# board.net
KiCad netlist of a schematic drawn in EAGLE
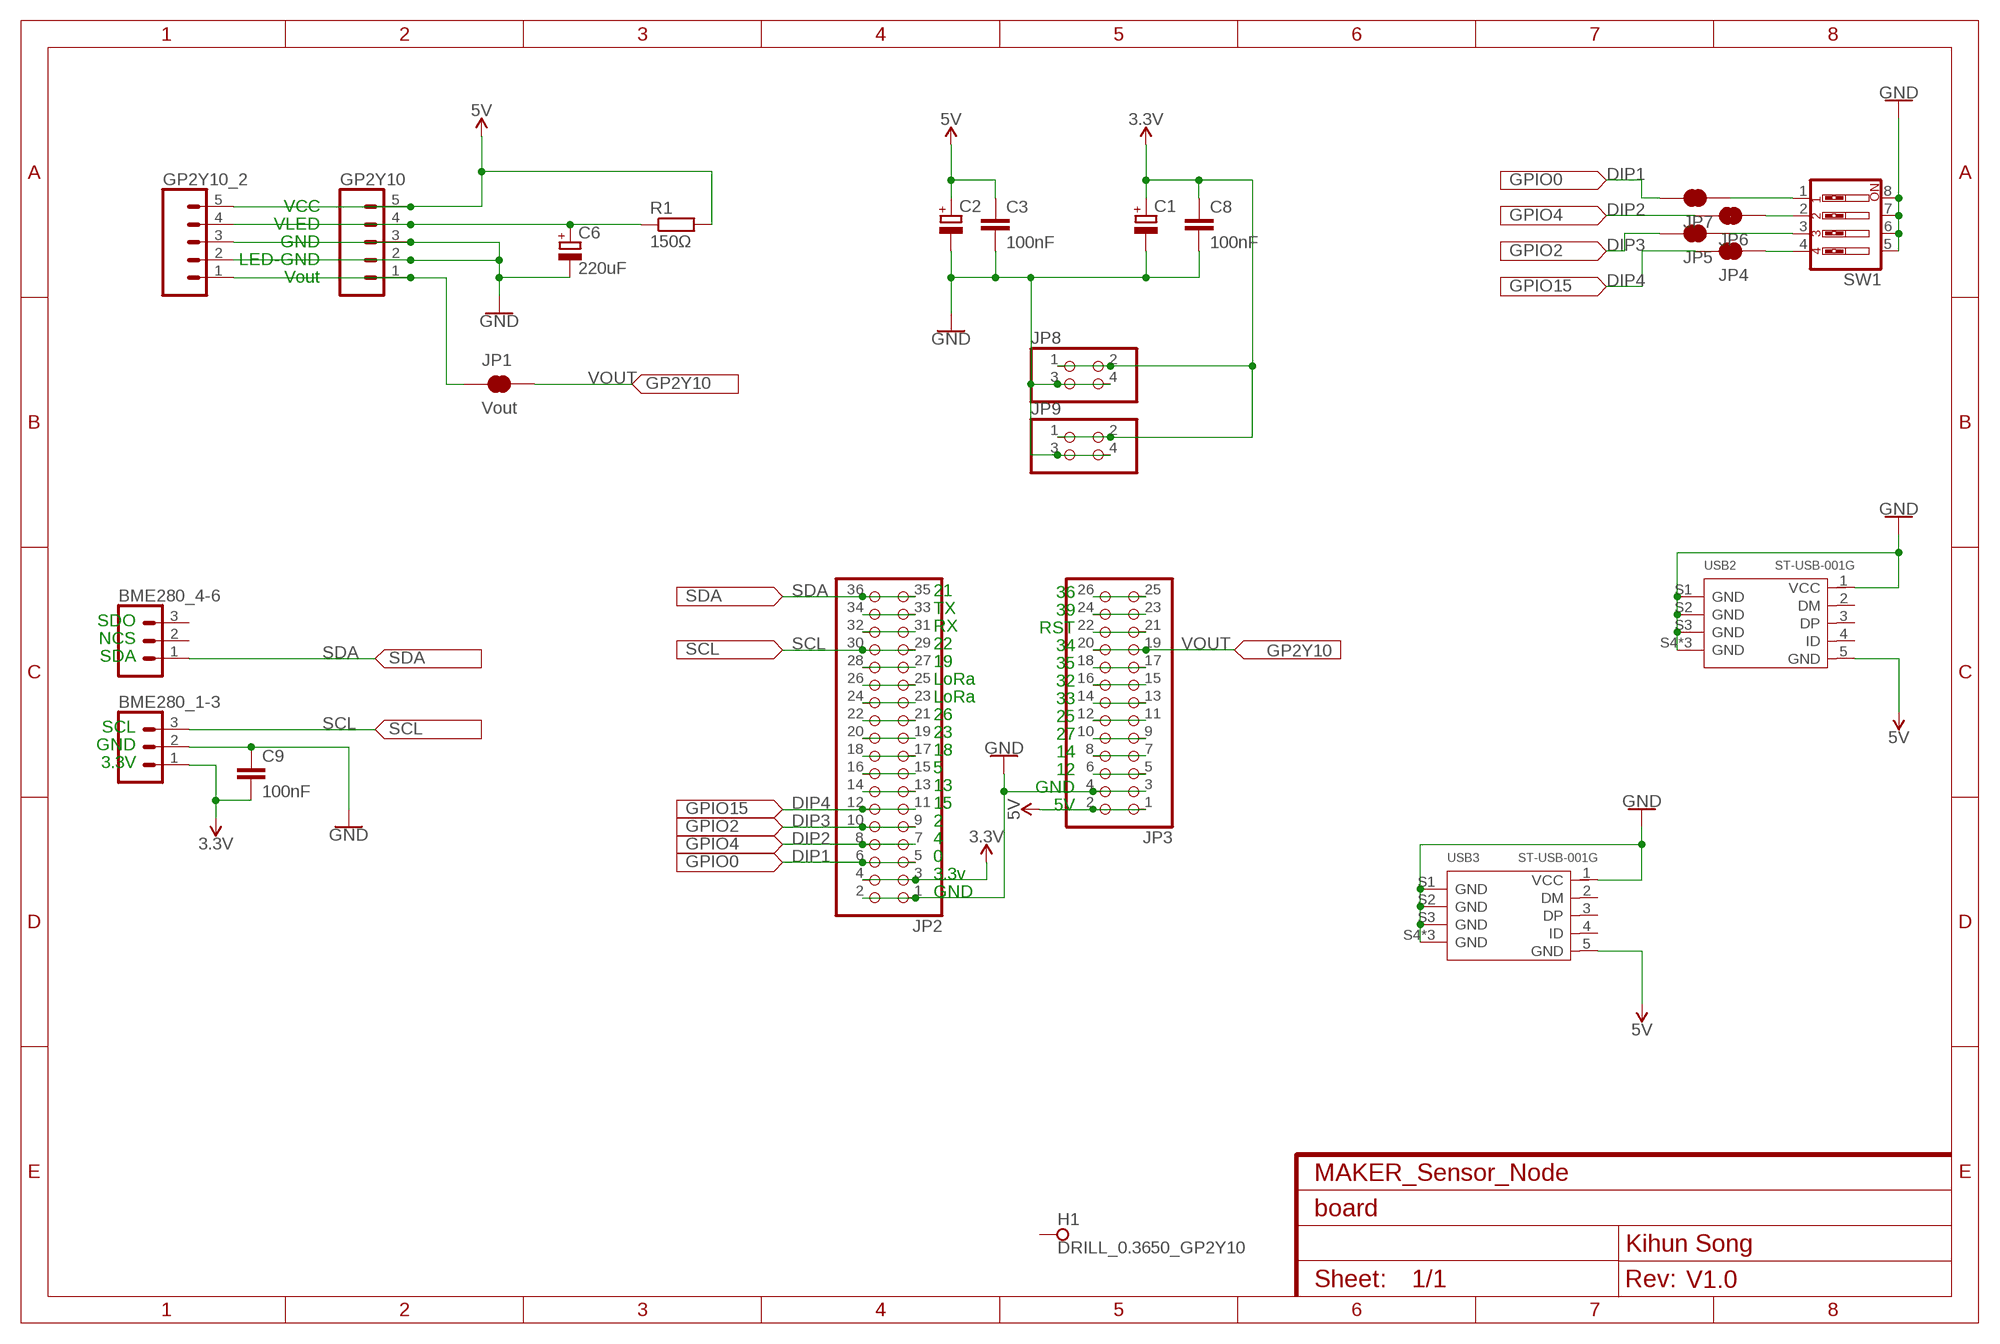
[diagram p0: schematic, sheet 1]

(export (version "E")
  (design (tool "Eeschema 10.0.6"))
  (components
    (comp (ref "BME280_1-3")
      (value "CONN_03")
      (footprint "eagle-import:1X03")
      (libsource (lib "eagle-import") (part "CONN_03"))
    )
    (comp (ref "BME280_4-6")
      (value "CONN_03")
      (footprint "eagle-import:1X03")
      (libsource (lib "eagle-import") (part "CONN_03"))
    )
    (comp (ref "C1")
      (value "CPOL-EUD")
      (footprint "eagle-import:PANASONIC_D")
      (libsource (lib "eagle-import") (part "CPOL-EUD"))
    )
    (comp (ref "C2")
      (value "CPOL-EUD")
      (footprint "eagle-import:PANASONIC_D")
      (libsource (lib "eagle-import") (part "CPOL-EUD"))
    )
    (comp (ref "C3")
      (value "100nF")
      (footprint "eagle-import:C0805")
      (libsource (lib "eagle-import") (part "C-EUC0805"))
    )
    (comp (ref "C6")
      (value "220uF")
      (footprint "eagle-import:E2,5-5")
      (libsource (lib "eagle-import") (part "CPOL-EUE2.5-5"))
    )
    (comp (ref "C8")
      (value "100nF")
      (footprint "eagle-import:C0805")
      (libsource (lib "eagle-import") (part "C-EUC0805"))
    )
    (comp (ref "C9")
      (value "100nF")
      (footprint "eagle-import:C0805")
      (libsource (lib "eagle-import") (part "C-EUC0805"))
    )
    (comp (ref "GP2Y10")
      (value "CONN_05")
      (footprint "eagle-import:1X05")
      (libsource (lib "eagle-import") (part "CONN_05"))
    )
    (comp (ref "GP2Y10_2")
      (value "CONN_05PTH_LONGPADS")
      (footprint "eagle-import:1X05_LONGPADS")
      (libsource (lib "eagle-import") (part "CONN_05PTH_LONGPADS"))
    )
    (comp (ref "H1")
      (value "DRILL_0.3650_GP2Y10")
      (footprint "eagle-import:PAD_0.3650")
      (libsource (lib "eagle-import") (part "SPECIAL_DRILL_0.3650"))
    )
    (comp (ref "JP1")
      (value "Vout")
      (footprint "eagle-import:SMT-JUMPER_2_NC_TRACE_SILK")
      (libsource (lib "eagle-import") (part "JUMPER-SMT_2_NC_TRACE_SILK"))
    )
    (comp (ref "JP2")
      (value "PINHD-2X18")
      (footprint "eagle-import:2X18")
      (libsource (lib "eagle-import") (part "PINHD-2X18"))
    )
    (comp (ref "JP3")
      (value "PINHD-2X13")
      (footprint "eagle-import:2X13")
      (libsource (lib "eagle-import") (part "PINHD-2X13"))
    )
    (comp (ref "JP4")
      (value "JUMPER-SMT_2_NC_TRACE_SILK")
      (footprint "eagle-import:SMT-JUMPER_2_NC_TRACE_SILK")
      (libsource (lib "eagle-import") (part "JUMPER-SMT_2_NC_TRACE_SILK"))
    )
    (comp (ref "JP5")
      (value "JUMPER-SMT_2_NC_TRACE_SILK")
      (footprint "eagle-import:SMT-JUMPER_2_NC_TRACE_SILK")
      (libsource (lib "eagle-import") (part "JUMPER-SMT_2_NC_TRACE_SILK"))
    )
    (comp (ref "JP6")
      (value "JUMPER-SMT_2_NC_TRACE_SILK")
      (footprint "eagle-import:SMT-JUMPER_2_NC_TRACE_SILK")
      (libsource (lib "eagle-import") (part "JUMPER-SMT_2_NC_TRACE_SILK"))
    )
    (comp (ref "JP7")
      (value "JUMPER-SMT_2_NC_TRACE_SILK")
      (footprint "eagle-import:SMT-JUMPER_2_NC_TRACE_SILK")
      (libsource (lib "eagle-import") (part "JUMPER-SMT_2_NC_TRACE_SILK"))
    )
    (comp (ref "JP8")
      (value "PINHD-2X2/OCT")
      (footprint "eagle-import:2X02")
      (libsource (lib "eagle-import") (part "PINHD-2X2/OCT"))
    )
    (comp (ref "JP9")
      (value "PINHD-2X2/OCT")
      (footprint "eagle-import:2X02")
      (libsource (lib "eagle-import") (part "PINHD-2X2/OCT"))
    )
    (comp (ref "R1")
      (value "150Ω")
      (footprint "eagle-import:0204_7")
      (libsource (lib "eagle-import") (part "R-EU_0204/7"))
    )
    (comp (ref "SW1")
      (value "SW_DIP-4")
      (footprint "eagle-import:EDG-04")
      (libsource (lib "eagle-import") (part "SW_DIP-4"))
    )
    (comp (ref "USB2")
      (value "ST-USB-001G")
      (footprint "eagle-import:MICRO-USB5+4P-SMD-0.65-B")
      (libsource (lib "eagle-import") (part "MICRO-USB-SMD-B-WITHOUT-POST-W/P(ST-USB-001G)"))
    )
    (comp (ref "USB3")
      (value "ST-USB-001G")
      (footprint "eagle-import:MICRO-USB5+4P-SMD-0.65-B")
      (libsource (lib "eagle-import") (part "MICRO-USB-SMD-B-WITHOUT-POST-W/P(ST-USB-001G)"))
    )
  )
  (nets
    (net (code "1") (name "/DIP1") (class "Default")
      (node (ref "JP2") (pin "5") (pinfunction "5_5") (pintype "passive"))
      (node (ref "JP2") (pin "6") (pinfunction "6_6") (pintype "passive"))
      (node (ref "JP7") (pin "2") (pinfunction "2_2") (pintype "passive"))
    )
    (net (code "2") (name "/DIP2") (class "Default")
      (node (ref "JP2") (pin "7") (pinfunction "7_7") (pintype "passive"))
      (node (ref "JP2") (pin "8") (pinfunction "8_8") (pintype "passive"))
      (node (ref "JP6") (pin "2") (pinfunction "2_2") (pintype "passive"))
    )
    (net (code "3") (name "/DIP3") (class "Default")
      (node (ref "JP2") (pin "10") (pinfunction "10_10") (pintype "passive"))
      (node (ref "JP2") (pin "9") (pinfunction "9_9") (pintype "passive"))
      (node (ref "JP5") (pin "2") (pinfunction "2_2") (pintype "passive"))
    )
    (net (code "4") (name "/DIP4") (class "Default")
      (node (ref "JP2") (pin "11") (pinfunction "11_11") (pintype "passive"))
      (node (ref "JP2") (pin "12") (pinfunction "12_12") (pintype "passive"))
      (node (ref "JP4") (pin "2") (pinfunction "2_2") (pintype "passive"))
    )
    (net (code "5") (name "/SCL") (class "Default")
      (node (ref "BME280_1-3") (pin "3") (pinfunction "3_3") (pintype "passive"))
      (node (ref "JP2") (pin "29") (pinfunction "29_29") (pintype "passive"))
      (node (ref "JP2") (pin "30") (pinfunction "30_30") (pintype "passive"))
    )
    (net (code "6") (name "/SDA") (class "Default")
      (node (ref "BME280_4-6") (pin "1") (pinfunction "1_1") (pintype "passive"))
      (node (ref "JP2") (pin "35") (pinfunction "35_35") (pintype "passive"))
      (node (ref "JP2") (pin "36") (pinfunction "36_36") (pintype "passive"))
    )
    (net (code "7") (name "/VOUT") (class "Default")
      (node (ref "JP1") (pin "2") (pinfunction "2_2") (pintype "passive"))
      (node (ref "JP3") (pin "19") (pinfunction "19_19") (pintype "passive"))
      (node (ref "JP3") (pin "20") (pinfunction "20_20") (pintype "passive"))
    )
    (net (code "8") (name "3.3V") (class "Default")
      (node (ref "BME280_1-3") (pin "1") (pinfunction "1_1") (pintype "passive"))
      (node (ref "C1") (pin "+") (pinfunction "+_+") (pintype "passive"))
      (node (ref "C8") (pin "1") (pinfunction "1_1") (pintype "passive"))
      (node (ref "C9") (pin "2") (pinfunction "2_2") (pintype "passive"))
      (node (ref "JP2") (pin "3") (pinfunction "3_3") (pintype "passive"))
      (node (ref "JP2") (pin "4") (pinfunction "4_4") (pintype "passive"))
      (node (ref "JP8") (pin "1") (pinfunction "1_1") (pintype "passive"))
      (node (ref "JP8") (pin "2") (pinfunction "2_2") (pintype "passive"))
      (node (ref "JP9") (pin "1") (pinfunction "1_1") (pintype "passive"))
      (node (ref "JP9") (pin "2") (pinfunction "2_2") (pintype "passive"))
    )
    (net (code "9") (name "5V") (class "Default")
      (node (ref "C2") (pin "+") (pinfunction "+_+") (pintype "passive"))
      (node (ref "C3") (pin "1") (pinfunction "1_1") (pintype "passive"))
      (node (ref "GP2Y10") (pin "5") (pinfunction "5_5") (pintype "passive"))
      (node (ref "GP2Y10_2") (pin "5") (pinfunction "5_5") (pintype "passive"))
      (node (ref "JP3") (pin "1") (pinfunction "1_1") (pintype "passive"))
      (node (ref "JP3") (pin "2") (pinfunction "2_2") (pintype "passive"))
      (node (ref "R1") (pin "2") (pinfunction "2_2") (pintype "passive"))
      (node (ref "USB2") (pin "5") (pinfunction "GND_5") (pintype "bidirectional"))
      (node (ref "USB3") (pin "5") (pinfunction "GND_5") (pintype "bidirectional"))
    )
    (net (code "10") (name "GND") (class "Default")
      (node (ref "BME280_1-3") (pin "2") (pinfunction "2_2") (pintype "passive"))
      (node (ref "C1") (pin "-") (pinfunction "-_-") (pintype "passive"))
      (node (ref "C2") (pin "-") (pinfunction "-_-") (pintype "passive"))
      (node (ref "C3") (pin "2") (pinfunction "2_2") (pintype "passive"))
      (node (ref "C6") (pin "-") (pinfunction "-_-") (pintype "passive"))
      (node (ref "C8") (pin "2") (pinfunction "2_2") (pintype "passive"))
      (node (ref "C9") (pin "1") (pinfunction "1_1") (pintype "passive"))
      (node (ref "GP2Y10") (pin "2") (pinfunction "2_2") (pintype "passive"))
      (node (ref "GP2Y10") (pin "3") (pinfunction "3_3") (pintype "passive"))
      (node (ref "GP2Y10_2") (pin "2") (pinfunction "2_2") (pintype "passive"))
      (node (ref "GP2Y10_2") (pin "3") (pinfunction "3_3") (pintype "passive"))
      (node (ref "JP2") (pin "1") (pinfunction "1_1") (pintype "passive"))
      (node (ref "JP2") (pin "2") (pinfunction "2_2") (pintype "passive"))
      (node (ref "JP3") (pin "3") (pinfunction "3_3") (pintype "passive"))
      (node (ref "JP3") (pin "4") (pinfunction "4_4") (pintype "passive"))
      (node (ref "JP8") (pin "3") (pinfunction "3_3") (pintype "passive"))
      (node (ref "JP8") (pin "4") (pinfunction "4_4") (pintype "passive"))
      (node (ref "JP9") (pin "3") (pinfunction "3_3") (pintype "passive"))
      (node (ref "JP9") (pin "4") (pinfunction "4_4") (pintype "passive"))
      (node (ref "SW1") (pin "5") (pinfunction "5_5") (pintype "passive"))
      (node (ref "SW1") (pin "6") (pinfunction "6_6") (pintype "passive"))
      (node (ref "SW1") (pin "7") (pinfunction "7_7") (pintype "passive"))
      (node (ref "SW1") (pin "8") (pinfunction "8_8") (pintype "passive"))
      (node (ref "USB2") (pin "1") (pinfunction "VCC_1") (pintype "bidirectional"))
      (node (ref "USB2") (pin "S1") (pinfunction "GND_S1") (pintype "bidirectional"))
      (node (ref "USB2") (pin "S2") (pinfunction "GND_S2") (pintype "bidirectional"))
      (node (ref "USB2") (pin "S3") (pinfunction "GND_S3") (pintype "bidirectional"))
      (node (ref "USB2") (pin "S4") (pinfunction "GND_S4") (pintype "bidirectional"))
      (node (ref "USB2") (pin "S5") (pinfunction "GND_S5") (pintype "bidirectional"))
      (node (ref "USB2") (pin "S6") (pinfunction "GND_S6") (pintype "bidirectional"))
      (node (ref "USB3") (pin "1") (pinfunction "VCC_1") (pintype "bidirectional"))
      (node (ref "USB3") (pin "S1") (pinfunction "GND_S1") (pintype "bidirectional"))
      (node (ref "USB3") (pin "S2") (pinfunction "GND_S2") (pintype "bidirectional"))
      (node (ref "USB3") (pin "S3") (pinfunction "GND_S3") (pintype "bidirectional"))
      (node (ref "USB3") (pin "S4") (pinfunction "GND_S4") (pintype "bidirectional"))
      (node (ref "USB3") (pin "S5") (pinfunction "GND_S5") (pintype "bidirectional"))
      (node (ref "USB3") (pin "S6") (pinfunction "GND_S6") (pintype "bidirectional"))
    )
    (net (code "11") (name "Net-(C6-Pad+)") (class "Default")
      (node (ref "C6") (pin "+") (pinfunction "+_+") (pintype "passive"))
      (node (ref "GP2Y10") (pin "4") (pinfunction "4_4") (pintype "passive"))
      (node (ref "GP2Y10_2") (pin "4") (pinfunction "4_4") (pintype "passive"))
      (node (ref "R1") (pin "1") (pinfunction "1_1") (pintype "passive"))
    )
    (net (code "12") (name "Net-(GP2Y10-Pad1)") (class "Default")
      (node (ref "GP2Y10") (pin "1") (pinfunction "1_1") (pintype "passive"))
      (node (ref "GP2Y10_2") (pin "1") (pinfunction "1_1") (pintype "passive"))
      (node (ref "JP1") (pin "1") (pinfunction "1_1") (pintype "passive"))
    )
    (net (code "13") (name "Net-(JP2-Pad13)") (class "Default")
      (node (ref "JP2") (pin "13") (pinfunction "13_13") (pintype "passive"))
      (node (ref "JP2") (pin "14") (pinfunction "14_14") (pintype "passive"))
    )
    (net (code "14") (name "Net-(JP2-Pad15)") (class "Default")
      (node (ref "JP2") (pin "15") (pinfunction "15_15") (pintype "passive"))
      (node (ref "JP2") (pin "16") (pinfunction "16_16") (pintype "passive"))
    )
    (net (code "15") (name "Net-(JP2-Pad17)") (class "Default")
      (node (ref "JP2") (pin "17") (pinfunction "17_17") (pintype "passive"))
      (node (ref "JP2") (pin "18") (pinfunction "18_18") (pintype "passive"))
    )
    (net (code "16") (name "Net-(JP2-Pad19)") (class "Default")
      (node (ref "JP2") (pin "19") (pinfunction "19_19") (pintype "passive"))
      (node (ref "JP2") (pin "20") (pinfunction "20_20") (pintype "passive"))
    )
    (net (code "17") (name "Net-(JP2-Pad21)") (class "Default")
      (node (ref "JP2") (pin "21") (pinfunction "21_21") (pintype "passive"))
      (node (ref "JP2") (pin "22") (pinfunction "22_22") (pintype "passive"))
    )
    (net (code "18") (name "Net-(JP2-Pad23)") (class "Default")
      (node (ref "JP2") (pin "23") (pinfunction "23_23") (pintype "passive"))
      (node (ref "JP2") (pin "24") (pinfunction "24_24") (pintype "passive"))
    )
    (net (code "19") (name "Net-(JP2-Pad25)") (class "Default")
      (node (ref "JP2") (pin "25") (pinfunction "25_25") (pintype "passive"))
      (node (ref "JP2") (pin "26") (pinfunction "26_26") (pintype "passive"))
    )
    (net (code "20") (name "Net-(JP2-Pad27)") (class "Default")
      (node (ref "JP2") (pin "27") (pinfunction "27_27") (pintype "passive"))
      (node (ref "JP2") (pin "28") (pinfunction "28_28") (pintype "passive"))
    )
    (net (code "21") (name "Net-(JP2-Pad31)") (class "Default")
      (node (ref "JP2") (pin "31") (pinfunction "31_31") (pintype "passive"))
      (node (ref "JP2") (pin "32") (pinfunction "32_32") (pintype "passive"))
    )
    (net (code "22") (name "Net-(JP2-Pad33)") (class "Default")
      (node (ref "JP2") (pin "33") (pinfunction "33_33") (pintype "passive"))
      (node (ref "JP2") (pin "34") (pinfunction "34_34") (pintype "passive"))
    )
    (net (code "23") (name "Net-(JP3-Pad5)") (class "Default")
      (node (ref "JP3") (pin "5") (pinfunction "5_5") (pintype "passive"))
      (node (ref "JP3") (pin "6") (pinfunction "6_6") (pintype "passive"))
    )
    (net (code "24") (name "Net-(JP3-Pad7)") (class "Default")
      (node (ref "JP3") (pin "7") (pinfunction "7_7") (pintype "passive"))
      (node (ref "JP3") (pin "8") (pinfunction "8_8") (pintype "passive"))
    )
    (net (code "25") (name "Net-(JP3-Pad10)") (class "Default")
      (node (ref "JP3") (pin "10") (pinfunction "10_10") (pintype "passive"))
      (node (ref "JP3") (pin "9") (pinfunction "9_9") (pintype "passive"))
    )
    (net (code "26") (name "Net-(JP3-Pad11)") (class "Default")
      (node (ref "JP3") (pin "11") (pinfunction "11_11") (pintype "passive"))
      (node (ref "JP3") (pin "12") (pinfunction "12_12") (pintype "passive"))
    )
    (net (code "27") (name "Net-(JP3-Pad13)") (class "Default")
      (node (ref "JP3") (pin "13") (pinfunction "13_13") (pintype "passive"))
      (node (ref "JP3") (pin "14") (pinfunction "14_14") (pintype "passive"))
    )
    (net (code "28") (name "Net-(JP3-Pad15)") (class "Default")
      (node (ref "JP3") (pin "15") (pinfunction "15_15") (pintype "passive"))
      (node (ref "JP3") (pin "16") (pinfunction "16_16") (pintype "passive"))
    )
    (net (code "29") (name "Net-(JP3-Pad17)") (class "Default")
      (node (ref "JP3") (pin "17") (pinfunction "17_17") (pintype "passive"))
      (node (ref "JP3") (pin "18") (pinfunction "18_18") (pintype "passive"))
    )
    (net (code "30") (name "Net-(JP3-Pad21)") (class "Default")
      (node (ref "JP3") (pin "21") (pinfunction "21_21") (pintype "passive"))
      (node (ref "JP3") (pin "22") (pinfunction "22_22") (pintype "passive"))
    )
    (net (code "31") (name "Net-(JP3-Pad23)") (class "Default")
      (node (ref "JP3") (pin "23") (pinfunction "23_23") (pintype "passive"))
      (node (ref "JP3") (pin "24") (pinfunction "24_24") (pintype "passive"))
    )
    (net (code "32") (name "Net-(JP3-Pad25)") (class "Default")
      (node (ref "JP3") (pin "25") (pinfunction "25_25") (pintype "passive"))
      (node (ref "JP3") (pin "26") (pinfunction "26_26") (pintype "passive"))
    )
    (net (code "33") (name "Net-(JP4-Pad1)") (class "Default")
      (node (ref "JP4") (pin "1") (pinfunction "1_1") (pintype "passive"))
      (node (ref "SW1") (pin "4") (pinfunction "4_4") (pintype "passive"))
    )
    (net (code "34") (name "Net-(JP5-Pad1)") (class "Default")
      (node (ref "JP5") (pin "1") (pinfunction "1_1") (pintype "passive"))
      (node (ref "SW1") (pin "3") (pinfunction "3_3") (pintype "passive"))
    )
    (net (code "35") (name "Net-(JP6-Pad1)") (class "Default")
      (node (ref "JP6") (pin "1") (pinfunction "1_1") (pintype "passive"))
      (node (ref "SW1") (pin "2") (pinfunction "2_2") (pintype "passive"))
    )
    (net (code "36") (name "Net-(JP7-Pad1)") (class "Default")
      (node (ref "JP7") (pin "1") (pinfunction "1_1") (pintype "passive"))
      (node (ref "SW1") (pin "1") (pinfunction "1_1") (pintype "passive"))
    )
    (net (code "37") (name "unconnected-(BME280_4-6-Pad2)") (class "Default")
      (node (ref "BME280_4-6") (pin "2") (pinfunction "2_2") (pintype "passive"))
    )
    (net (code "38") (name "unconnected-(BME280_4-6-Pad3)") (class "Default")
      (node (ref "BME280_4-6") (pin "3") (pinfunction "3_3") (pintype "passive"))
    )
    (net (code "39") (name "unconnected-(H1-Pad1)") (class "Default")
      (node (ref "H1") (pin "1") (pinfunction "1_1") (pintype "passive"))
    )
    (net (code "40") (name "unconnected-(USB2-DM-Pad2)") (class "Default")
      (node (ref "USB2") (pin "2") (pinfunction "DM_2") (pintype "bidirectional"))
    )
    (net (code "41") (name "unconnected-(USB2-DP-Pad3)") (class "Default")
      (node (ref "USB2") (pin "3") (pinfunction "DP_3") (pintype "bidirectional"))
    )
    (net (code "42") (name "unconnected-(USB2-ID-Pad4)") (class "Default")
      (node (ref "USB2") (pin "4") (pinfunction "ID_4") (pintype "bidirectional"))
    )
    (net (code "43") (name "unconnected-(USB3-DM-Pad2)") (class "Default")
      (node (ref "USB3") (pin "2") (pinfunction "DM_2") (pintype "bidirectional"))
    )
    (net (code "44") (name "unconnected-(USB3-DP-Pad3)") (class "Default")
      (node (ref "USB3") (pin "3") (pinfunction "DP_3") (pintype "bidirectional"))
    )
    (net (code "45") (name "unconnected-(USB3-ID-Pad4)") (class "Default")
      (node (ref "USB3") (pin "4") (pinfunction "ID_4") (pintype "bidirectional"))
    )
  )
)
